# 5V_EFuse.net
KiCad netlist of a schematic drawn in Altium Designer
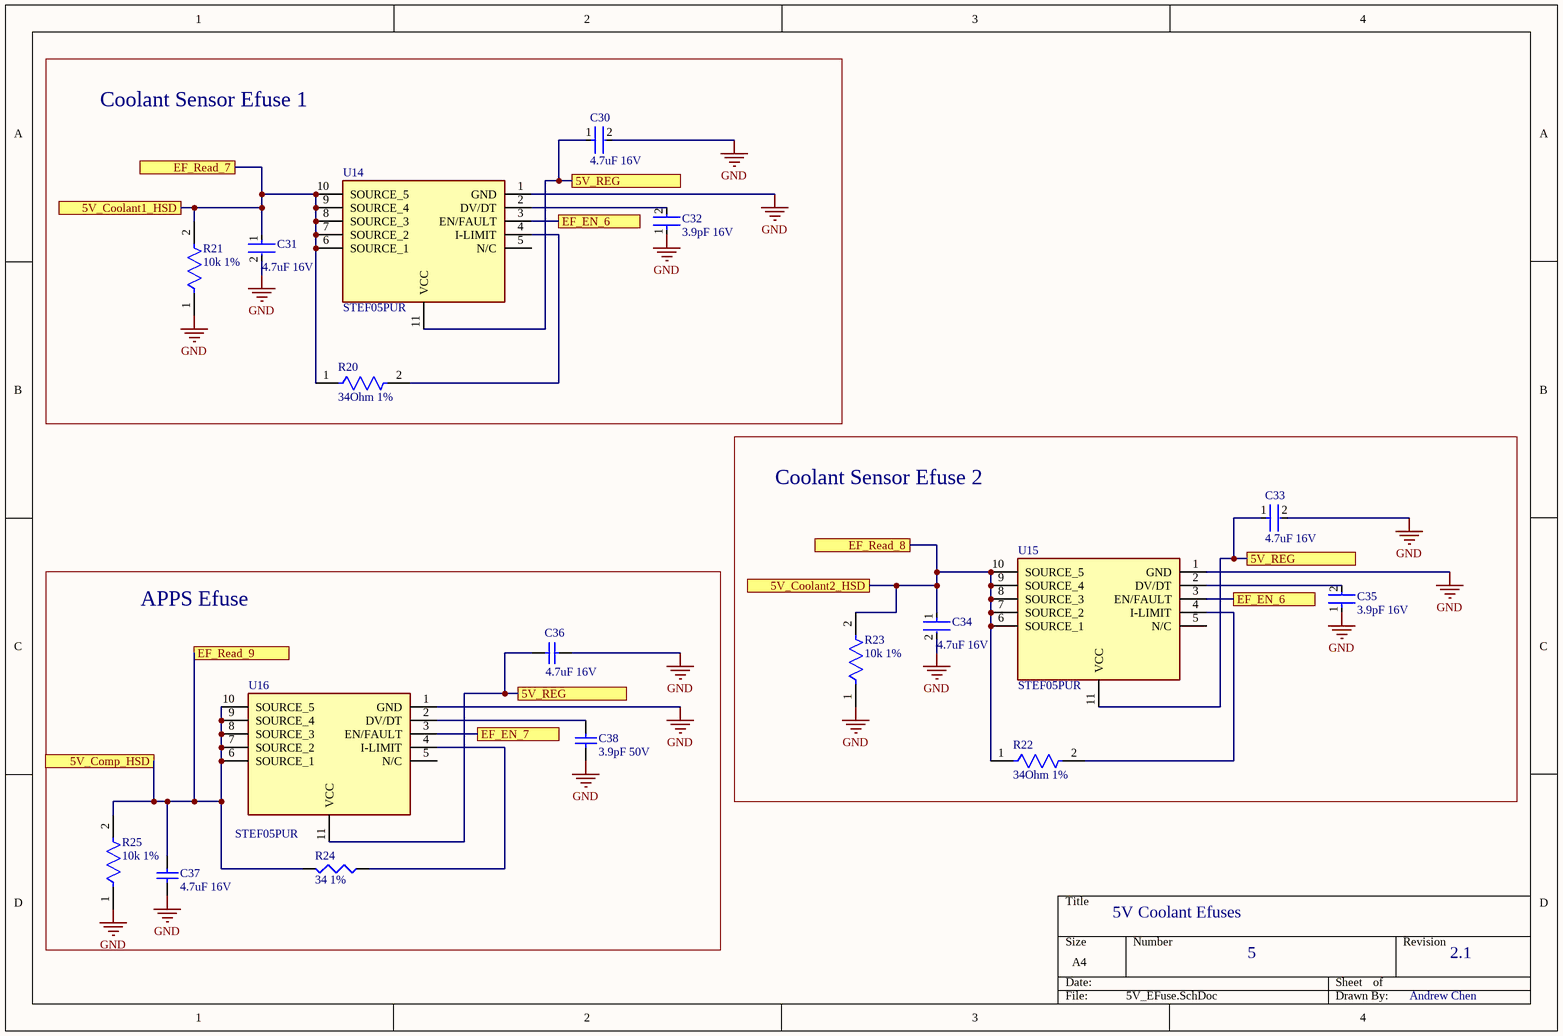
[diagram p0: 5V_EFuse.SchDoc]

(export (version "E")
  (design (tool "Eeschema 10.0.6"))
  (components
    (comp (ref "C30")
      (value "4.7uF 16V")
      (footprint "FP-CL31-IPC_A")
      (description "Cap Ceramic 4.7uF 16V X7R ±10% SMD 1206 +125°C Embossed T/R")
      (fields (field (name "TOLERANCE") "10%"))
      (libsource (lib "Altium Content Vault") (part "b4654b650e69147ec39a6b967a45e02"))
    )
    (comp (ref "C31")
      (value "4.7uF 16V")
      (footprint "FP-CL31-IPC_A")
      (description "Cap Ceramic 4.7uF 16V X7R ±10% SMD 1206 +125°C Embossed T/R")
      (fields (field (name "TOLERANCE") "10%"))
      (libsource (lib "Altium Content Vault") (part "b4654b650e69147ec39a6b967a45e02"))
    )
    (comp (ref "C32")
      (value "3.9pF 16V")
      (footprint "FP-CL31-IPC_A")
      (description "Cap Ceramic 4.7uF 16V X7R ±10% SMD 1206 +125°C Embossed T/R")
      (fields (field (name "TOLERANCE") "10%"))
      (libsource (lib "Altium Content Vault") (part "b4654b650e69147ec39a6b967a45e02"))
    )
    (comp (ref "C33")
      (value "4.7uF 16V")
      (footprint "FP-CL31-IPC_A")
      (description "Cap Ceramic 4.7uF 16V X7R ±10% SMD 1206 +125°C Embossed T/R")
      (fields (field (name "TOLERANCE") "10%"))
      (libsource (lib "Altium Content Vault") (part "b4654b650e69147ec39a6b967a45e02"))
    )
    (comp (ref "C34")
      (value "4.7uF 16V")
      (footprint "FP-CL31-IPC_A")
      (description "Cap Ceramic 4.7uF 16V X7R ±10% SMD 1206 +125°C Embossed T/R")
      (fields (field (name "TOLERANCE") "10%"))
      (libsource (lib "Altium Content Vault") (part "b4654b650e69147ec39a6b967a45e02"))
    )
    (comp (ref "C35")
      (value "3.9pF 16V")
      (footprint "FP-CL31-IPC_A")
      (description "Cap Ceramic 4.7uF 16V X7R ±10% SMD 1206 +125°C Embossed T/R")
      (fields (field (name "TOLERANCE") "10%"))
      (libsource (lib "Altium Content Vault") (part "b4654b650e69147ec39a6b967a45e02"))
    )
    (comp (ref "C36")
      (value "4.7uF 16V")
      (footprint "C1206")
      (description "Capacitor (Semiconductor SIM Model)")
      (fields (field (name "PUBLISHER") "Altium Limited"))
      (libsource (lib "Miscellaneous Devices") (part "Cap Semi"))
    )
    (comp (ref "C37")
      (value "4.7uF 16V")
      (footprint "C1206")
      (description "Capacitor (Semiconductor SIM Model)")
      (fields (field (name "PUBLISHER") "Altium Limited"))
      (libsource (lib "Miscellaneous Devices") (part "Cap Semi"))
    )
    (comp (ref "C38")
      (value "3.9pF 50V")
      (footprint "C1206")
      (description "Capacitor (Semiconductor SIM Model)")
      (fields (field (name "PUBLISHER") "Altium Limited"))
      (libsource (lib "Miscellaneous Devices") (part "Cap Semi"))
    )
    (comp (ref "R20")
      (value "34Ohm 1%")
      (footprint "FP-CRCW0603-e3-IPC_B")
      (description "RES Thick Film, 18Ω, 1%, 0.1W, 100ppm/°C, 0603")
      (fields (field (name "TOLERANCE") "1%"))
      (libsource (lib "Altium Content Vault") (part "1029c3af85768c4190bb7ad29bc67b5"))
    )
    (comp (ref "R21")
      (value "10k 1%")
      (footprint "FP-CRCW0603-e3-IPC_B")
      (description "RES Thick Film, 18Ω, 1%, 0.1W, 100ppm/°C, 0603")
      (fields (field (name "TOLERANCE") "1%"))
      (libsource (lib "Altium Content Vault") (part "1029c3af85768c4190bb7ad29bc67b5"))
    )
    (comp (ref "R22")
      (value "34Ohm 1%")
      (footprint "FP-CRCW0603-e3-IPC_B")
      (description "RES Thick Film, 18Ω, 1%, 0.1W, 100ppm/°C, 0603")
      (fields (field (name "TOLERANCE") "1%"))
      (libsource (lib "Altium Content Vault") (part "1029c3af85768c4190bb7ad29bc67b5"))
    )
    (comp (ref "R23")
      (value "10k 1%")
      (footprint "FP-CRCW0603-e3-IPC_B")
      (description "RES Thick Film, 18Ω, 1%, 0.1W, 100ppm/°C, 0603")
      (fields (field (name "TOLERANCE") "1%"))
      (libsource (lib "Altium Content Vault") (part "1029c3af85768c4190bb7ad29bc67b5"))
    )
    (comp (ref "R24")
      (value "34 1%")
      (footprint "J1-0603")
      (description "Resistor")
      (fields (field (name "PUBLISHER") "Altium Limited"))
      (libsource (lib "Miscellaneous Devices") (part "Res3"))
    )
    (comp (ref "R25")
      (value "10k 1%")
      (footprint "FP-CRCW0603-e3-IPC_B")
      (description "RES Thick Film, 18Ω, 1%, 0.1W, 100ppm/°C, 0603")
      (fields (field (name "TOLERANCE") "1%"))
      (libsource (lib "Altium Content Vault") (part "1029c3af85768c4190bb7ad29bc67b5"))
    )
    (comp (ref "U14")
      (value "STEF05PUR")
      (footprint "SON50P300X300X100-11N-D")
      (description "Integrated Circuit")
      (fields
        (field (name "MANUFACTURER_PART_NUMBER") "STEF12EPUR")
        (field (name "MOUSER PART NUMBER") "511-STEF12EPUR")
      )
      (libsource (lib "*") (part "STEF12EPUR"))
    )
    (comp (ref "U15")
      (value "STEF05PUR")
      (footprint "SON50P300X300X100-11N-D")
      (description "Integrated Circuit")
      (fields
        (field (name "MANUFACTURER_PART_NUMBER") "STEF12EPUR")
        (field (name "MOUSER PART NUMBER") "511-STEF12EPUR")
      )
      (libsource (lib "*") (part "STEF12EPUR"))
    )
    (comp (ref "U16")
      (value "STEF05PUR")
      (footprint "SON50P300X300X100-11N-D")
      (description "Integrated Circuit")
      (fields
        (field (name "MANUFACTURER_PART_NUMBER") "STEF12EPUR")
        (field (name "MOUSER PART NUMBER") "511-STEF12EPUR")
      )
      (libsource (lib "*") (part "STEF12EPUR"))
    )
  )
  (nets
    (net (code "1") (name "/5V_Comp_HSD") (class "Default")
      (node (ref "C37") (pin "1") (pinfunction "1_1") (pintype "passive"))
      (node (ref "R24") (pin "2") (pinfunction "2_2") (pintype "passive"))
      (node (ref "R25") (pin "2") (pinfunction "2_2") (pintype "passive"))
      (node (ref "U16") (pin "10") (pinfunction "SOURCE_5_10") (pintype "passive"))
      (node (ref "U16") (pin "6") (pinfunction "SOURCE_1_6") (pintype "passive"))
      (node (ref "U16") (pin "7") (pinfunction "SOURCE_2_7") (pintype "passive"))
      (node (ref "U16") (pin "8") (pinfunction "SOURCE_3_8") (pintype "passive"))
      (node (ref "U16") (pin "9") (pinfunction "SOURCE_4_9") (pintype "passive"))
    )
    (net (code "2") (name "/5V_Coolant1_HSD") (class "Default")
      (node (ref "C31") (pin "1") (pinfunction "1_1") (pintype "passive"))
      (node (ref "R20") (pin "1") (pinfunction "1_1") (pintype "passive"))
      (node (ref "R21") (pin "2") (pinfunction "2_2") (pintype "passive"))
      (node (ref "U14") (pin "10") (pinfunction "SOURCE_5_10") (pintype "passive"))
      (node (ref "U14") (pin "6") (pinfunction "SOURCE_1_6") (pintype "passive"))
      (node (ref "U14") (pin "7") (pinfunction "SOURCE_2_7") (pintype "passive"))
      (node (ref "U14") (pin "8") (pinfunction "SOURCE_3_8") (pintype "passive"))
      (node (ref "U14") (pin "9") (pinfunction "SOURCE_4_9") (pintype "passive"))
    )
    (net (code "3") (name "/5V_Coolant2_HSD") (class "Default")
      (node (ref "C34") (pin "1") (pinfunction "1_1") (pintype "passive"))
      (node (ref "R22") (pin "1") (pinfunction "1_1") (pintype "passive"))
      (node (ref "R23") (pin "2") (pinfunction "2_2") (pintype "passive"))
      (node (ref "U15") (pin "10") (pinfunction "SOURCE_5_10") (pintype "passive"))
      (node (ref "U15") (pin "6") (pinfunction "SOURCE_1_6") (pintype "passive"))
      (node (ref "U15") (pin "7") (pinfunction "SOURCE_2_7") (pintype "passive"))
      (node (ref "U15") (pin "8") (pinfunction "SOURCE_3_8") (pintype "passive"))
      (node (ref "U15") (pin "9") (pinfunction "SOURCE_4_9") (pintype "passive"))
    )
    (net (code "4") (name "/5V_REG") (class "Default")
      (node (ref "C30") (pin "1") (pinfunction "1_1") (pintype "passive"))
      (node (ref "C33") (pin "1") (pinfunction "1_1") (pintype "passive"))
      (node (ref "C36") (pin "1") (pinfunction "1_1") (pintype "passive"))
      (node (ref "U14") (pin "11") (pinfunction "VCC_11") (pintype "passive"))
      (node (ref "U15") (pin "11") (pinfunction "VCC_11") (pintype "passive"))
      (node (ref "U16") (pin "11") (pinfunction "VCC_11") (pintype "passive"))
    )
    (net (code "5") (name "/EF_EN_6") (class "Default")
      (node (ref "U14") (pin "3") (pinfunction "EN/FAULT_3") (pintype "passive"))
      (node (ref "U15") (pin "3") (pinfunction "EN/FAULT_3") (pintype "passive"))
    )
    (net (code "6") (name "/EF_EN_7") (class "Default")
      (node (ref "U16") (pin "3") (pinfunction "EN/FAULT_3") (pintype "passive"))
    )
    (net (code "7") (name "GND") (class "Default")
      (node (ref "C30") (pin "2") (pinfunction "2_2") (pintype "passive"))
      (node (ref "C31") (pin "2") (pinfunction "2_2") (pintype "passive"))
      (node (ref "C32") (pin "1") (pinfunction "1_1") (pintype "passive"))
      (node (ref "C33") (pin "2") (pinfunction "2_2") (pintype "passive"))
      (node (ref "C34") (pin "2") (pinfunction "2_2") (pintype "passive"))
      (node (ref "C35") (pin "1") (pinfunction "1_1") (pintype "passive"))
      (node (ref "C36") (pin "2") (pinfunction "2_2") (pintype "passive"))
      (node (ref "C37") (pin "2") (pinfunction "2_2") (pintype "passive"))
      (node (ref "C38") (pin "2") (pinfunction "2_2") (pintype "passive"))
      (node (ref "R21") (pin "1") (pinfunction "1_1") (pintype "passive"))
      (node (ref "R23") (pin "1") (pinfunction "1_1") (pintype "passive"))
      (node (ref "R25") (pin "1") (pinfunction "1_1") (pintype "passive"))
      (node (ref "U14") (pin "1") (pinfunction "GND_1") (pintype "passive"))
      (node (ref "U15") (pin "1") (pinfunction "GND_1") (pintype "passive"))
      (node (ref "U16") (pin "1") (pinfunction "GND_1") (pintype "passive"))
    )
    (net (code "8") (name "Net-(U14-DV{slash}DT)") (class "Default")
      (node (ref "C32") (pin "2") (pinfunction "2_2") (pintype "passive"))
      (node (ref "U14") (pin "2") (pinfunction "DV/DT_2") (pintype "passive"))
    )
    (net (code "9") (name "Net-(U14-I-LIMIT)") (class "Default")
      (node (ref "R20") (pin "2") (pinfunction "2_2") (pintype "passive"))
      (node (ref "U14") (pin "4") (pinfunction "I-LIMIT_4") (pintype "passive"))
    )
    (net (code "10") (name "Net-(U15-DV{slash}DT)") (class "Default")
      (node (ref "C35") (pin "2") (pinfunction "2_2") (pintype "passive"))
      (node (ref "U15") (pin "2") (pinfunction "DV/DT_2") (pintype "passive"))
    )
    (net (code "11") (name "Net-(U15-I-LIMIT)") (class "Default")
      (node (ref "R22") (pin "2") (pinfunction "2_2") (pintype "passive"))
      (node (ref "U15") (pin "4") (pinfunction "I-LIMIT_4") (pintype "passive"))
    )
    (net (code "12") (name "Net-(U16-DV{slash}DT)") (class "Default")
      (node (ref "C38") (pin "1") (pinfunction "1_1") (pintype "passive"))
      (node (ref "U16") (pin "2") (pinfunction "DV/DT_2") (pintype "passive"))
    )
    (net (code "13") (name "Net-(U16-I-LIMIT)") (class "Default")
      (node (ref "R24") (pin "1") (pinfunction "1_1") (pintype "passive"))
      (node (ref "U16") (pin "4") (pinfunction "I-LIMIT_4") (pintype "passive"))
    )
    (net (code "14") (name "unconnected-(U14-N{slash}C-Pad5)") (class "Default")
      (node (ref "U14") (pin "5") (pinfunction "N/C_5") (pintype "passive"))
    )
    (net (code "15") (name "unconnected-(U15-N{slash}C-Pad5)") (class "Default")
      (node (ref "U15") (pin "5") (pinfunction "N/C_5") (pintype "passive"))
    )
    (net (code "16") (name "unconnected-(U16-N{slash}C-Pad5)") (class "Default")
      (node (ref "U16") (pin "5") (pinfunction "N/C_5") (pintype "passive"))
    )
  )
)
